# LCD-Touch.net
KiCad netlist of a schematic drawn in Altium Designer
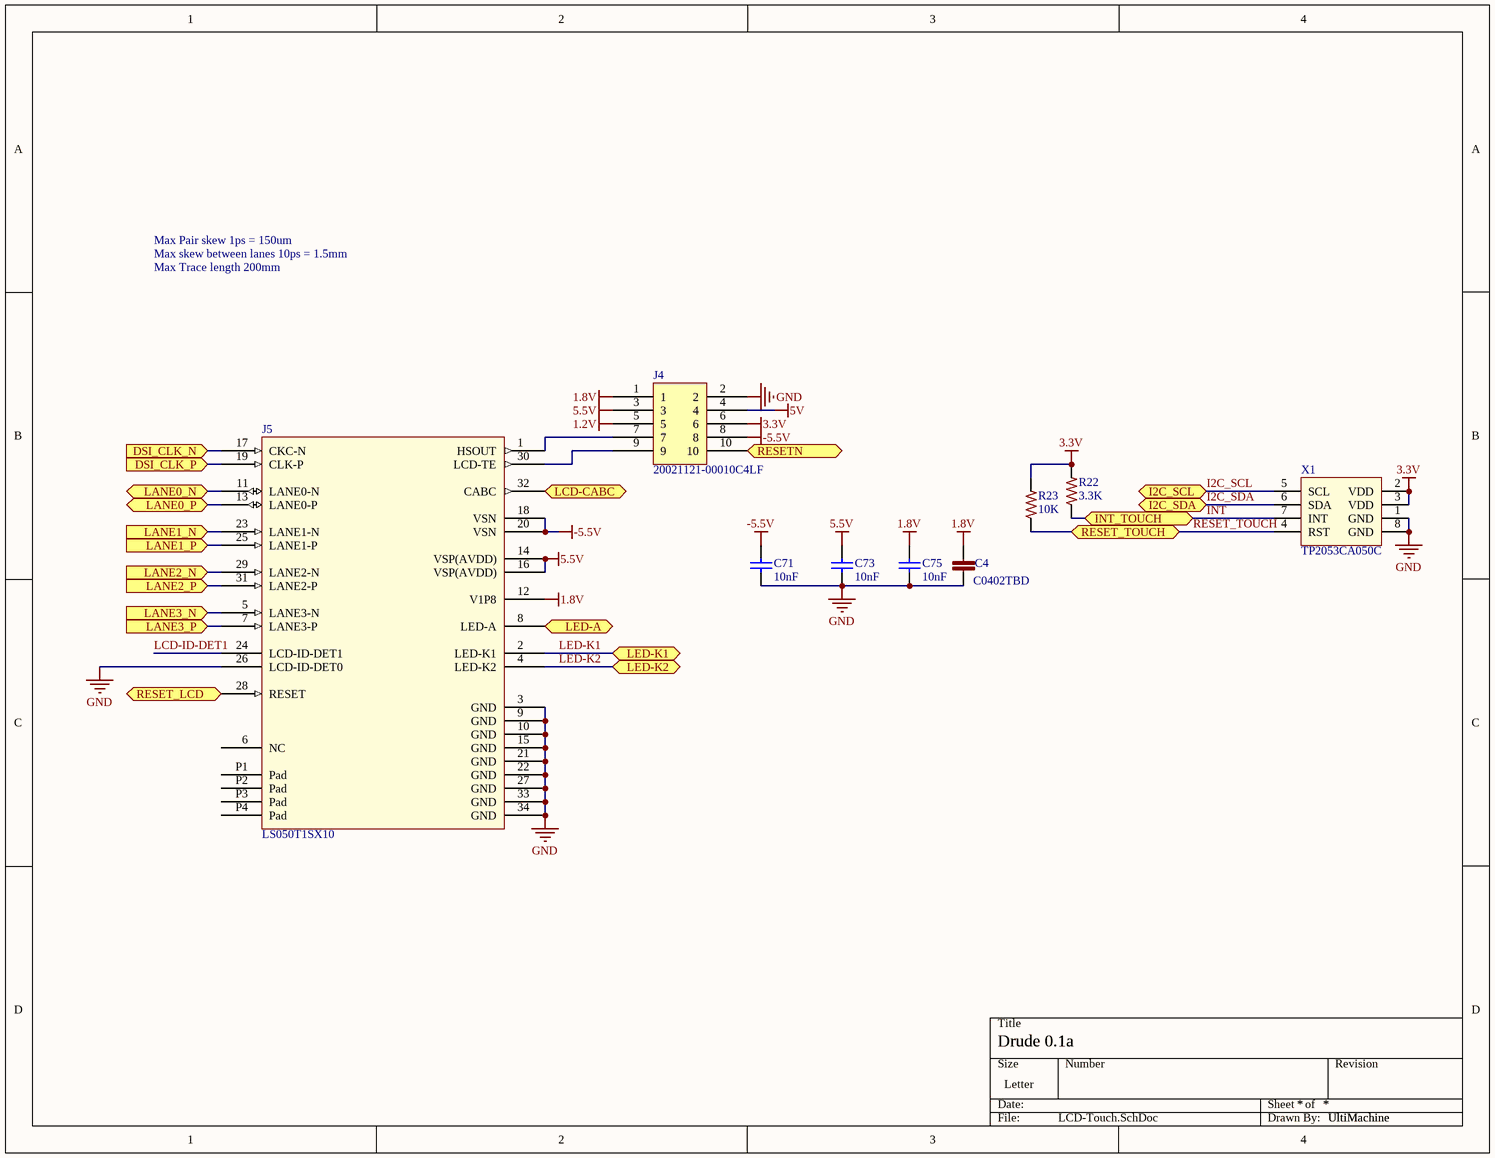
[diagram p0: LCD-Touch.SchDoc]

(export (version "E")
  (design (tool "Eeschema 10.0.6"))
  (components
    (comp (ref "C4")
      (value "C0402TBD")
      (footprint "C0402")
      (description "Capacitor Non Polarized")
      (fields (field (name "PUBLISHER") "UltiMachine"))
      (libsource (lib "3Delight") (part "C0402TBD"))
    )
    (comp (ref "C71")
      (value "10nF")
      (footprint "C0402")
      (description "CAP CER 10nF 50V X7R 0402")
      (fields
        (field (name "MFR PART #") "GRM155R71H103JA88D")
        (field (name "MFR") "Murata")
        (field (name "PUBLISHER") "Ultimachine")
      )
      (libsource (lib "hmi") (part "GRM155R71H103JA88D"))
    )
    (comp (ref "C73")
      (value "10nF")
      (footprint "C0402")
      (description "CAP CER 10nF 50V X7R 0402")
      (fields
        (field (name "MFR PART #") "GRM155R71H103JA88D")
        (field (name "MFR") "Murata")
        (field (name "PUBLISHER") "Ultimachine")
      )
      (libsource (lib "hmi") (part "GRM155R71H103JA88D"))
    )
    (comp (ref "C75")
      (value "10nF")
      (footprint "C0402")
      (description "CAP CER 10nF 50V X7R 0402")
      (fields
        (field (name "MFR PART #") "GRM155R71H103JA88D")
        (field (name "MFR") "Murata")
        (field (name "PUBLISHER") "Ultimachine")
      )
      (libsource (lib "hmi") (part "GRM155R71H103JA88D"))
    )
    (comp (ref "J4")
      (value "20021121-00010C4LF")
      (footprint "FTSH-105-XX-X-DV")
      (libsource (lib "Adams Altium Library") (part "ARM Cortex JTAG-DEBUG Header"))
    )
    (comp (ref "J5")
      (value "LS050T1SX10")
      (footprint "504208-3410")
      (description "5\"HD LCD Module connector")
      (libsource (lib "hmi") (part "LS050T1SX10"))
    )
    (comp (ref "R22")
      (value "3.3K")
      (footprint "R0603")
      (description "RES 0603 3.3K 100mW 1%")
      (fields
        (field (name "MANUFACTURERPARTNUMBER") "ERJ-3EKF1002V")
        (field (name "PUBLISHER") "UltiMachine")
      )
      (libsource (lib "hmi") (part "ERJ-3GEYJ332V"))
    )
    (comp (ref "R23")
      (value "10K")
      (footprint "R0402")
      (description "RES SMD 10K OHM 1% 1/16W 0402")
      (fields
        (field (name "MANUFACTURERPARTNUMBER") "RC0402FR-0710KP")
        (field (name "PUBLISHER") "UltiMachine")
      )
      (libsource (lib "3Delight") (part "RC0402FR-0710KP"))
    )
    (comp (ref "X1")
      (value "TP2053CA050C")
      (footprint "FFC8x05-top")
      (description "UltiMachine 5\" HD Touch Interface")
      (libsource (lib "hmi") (part "TP2053CA050C"))
    )
  )
  (nets
    (net (code "1") (name "-5.5V") (class "Default")
      (node (ref "C71") (pin "2") (pinfunction "2_2") (pintype "passive"))
      (node (ref "J4") (pin "8") (pinfunction "8_8") (pintype "passive"))
      (node (ref "J5") (pin "18") (pinfunction "VSN_18") (pintype "power_in"))
      (node (ref "J5") (pin "20") (pinfunction "VSN_20") (pintype "power_in"))
    )
    (net (code "2") (name "/DSI_CLK_N") (class "Default")
      (node (ref "J5") (pin "17") (pinfunction "CKC-N_17") (pintype "input"))
    )
    (net (code "3") (name "/DSI_CLK_P") (class "Default")
      (node (ref "J5") (pin "19") (pinfunction "CLK-P_19") (pintype "input"))
    )
    (net (code "4") (name "/I2C_SCL") (class "Default")
      (node (ref "X1") (pin "5") (pinfunction "SCL_5") (pintype "power_in"))
    )
    (net (code "5") (name "/I2C_SDA") (class "Default")
      (node (ref "X1") (pin "6") (pinfunction "SDA_6") (pintype "power_in"))
    )
    (net (code "6") (name "/INT") (class "Default")
      (node (ref "R22") (pin "1") (pinfunction "1_1") (pintype "passive"))
      (node (ref "X1") (pin "7") (pinfunction "INT_7") (pintype "power_in"))
    )
    (net (code "7") (name "/LANE0_N") (class "Default")
      (node (ref "J5") (pin "11") (pinfunction "LANE0-N_11") (pintype "bidirectional"))
    )
    (net (code "8") (name "/LANE0_P") (class "Default")
      (node (ref "J5") (pin "13") (pinfunction "LANE0-P_13") (pintype "bidirectional"))
    )
    (net (code "9") (name "/LANE1_N") (class "Default")
      (node (ref "J5") (pin "23") (pinfunction "LANE1-N_23") (pintype "input"))
    )
    (net (code "10") (name "/LANE1_P") (class "Default")
      (node (ref "J5") (pin "25") (pinfunction "LANE1-P_25") (pintype "input"))
    )
    (net (code "11") (name "/LANE2_N") (class "Default")
      (node (ref "J5") (pin "29") (pinfunction "LANE2-N_29") (pintype "input"))
    )
    (net (code "12") (name "/LANE2_P") (class "Default")
      (node (ref "J5") (pin "31") (pinfunction "LANE2-P_31") (pintype "input"))
    )
    (net (code "13") (name "/LANE3_N") (class "Default")
      (node (ref "J5") (pin "5") (pinfunction "LANE3-N_5") (pintype "input"))
    )
    (net (code "14") (name "/LANE3_P") (class "Default")
      (node (ref "J5") (pin "7") (pinfunction "LANE3-P_7") (pintype "input"))
    )
    (net (code "15") (name "/LCD-CABC") (class "Default")
      (node (ref "J5") (pin "32") (pinfunction "CABC_32") (pintype "output"))
    )
    (net (code "16") (name "/LCD-ID-DET1") (class "Default")
      (node (ref "J5") (pin "24") (pinfunction "LCD-ID-DET1_24") (pintype "passive"))
    )
    (net (code "17") (name "/LED-A") (class "Default")
      (node (ref "J5") (pin "8") (pinfunction "LED-A_8") (pintype "power_in"))
    )
    (net (code "18") (name "/LED-K1") (class "Default")
      (node (ref "J5") (pin "2") (pinfunction "LED-K1_2") (pintype "power_in"))
    )
    (net (code "19") (name "/LED-K2") (class "Default")
      (node (ref "J5") (pin "4") (pinfunction "LED-K2_4") (pintype "power_in"))
    )
    (net (code "20") (name "/RESETN") (class "Default")
      (node (ref "J4") (pin "10") (pinfunction "10_10") (pintype "passive"))
    )
    (net (code "21") (name "/RESET_LCD") (class "Default")
      (node (ref "J5") (pin "28") (pinfunction "RESET_28") (pintype "input"))
    )
    (net (code "22") (name "/RESET_TOUCH") (class "Default")
      (node (ref "R23") (pin "1") (pinfunction "1_1") (pintype "passive"))
      (node (ref "X1") (pin "4") (pinfunction "RST_4") (pintype "power_in"))
    )
    (net (code "23") (name "1.2V") (class "Default")
      (node (ref "J4") (pin "5") (pinfunction "5_5") (pintype "passive"))
    )
    (net (code "24") (name "1.8V") (class "Default")
      (node (ref "C4") (pin "1") (pinfunction "1_1") (pintype "passive"))
      (node (ref "C75") (pin "2") (pinfunction "2_2") (pintype "passive"))
      (node (ref "J4") (pin "1") (pinfunction "1_1") (pintype "passive"))
      (node (ref "J5") (pin "12") (pinfunction "V1P8_12") (pintype "power_in"))
    )
    (net (code "25") (name "3.3V") (class "Default")
      (node (ref "J4") (pin "6") (pinfunction "6_6") (pintype "passive"))
      (node (ref "R22") (pin "2") (pinfunction "2_2") (pintype "passive"))
      (node (ref "R23") (pin "2") (pinfunction "2_2") (pintype "passive"))
      (node (ref "X1") (pin "2") (pinfunction "VDD_2") (pintype "power_in"))
      (node (ref "X1") (pin "3") (pinfunction "VDD_3") (pintype "power_in"))
    )
    (net (code "26") (name "5.5V") (class "Default")
      (node (ref "C73") (pin "2") (pinfunction "2_2") (pintype "passive"))
      (node (ref "J4") (pin "3") (pinfunction "3_3") (pintype "passive"))
      (node (ref "J5") (pin "14") (pinfunction "VSP(AVDD)_14") (pintype "power_in"))
      (node (ref "J5") (pin "16") (pinfunction "VSP(AVDD)_16") (pintype "power_in"))
    )
    (net (code "27") (name "5V") (class "Default")
      (node (ref "J4") (pin "4") (pinfunction "4_4") (pintype "passive"))
    )
    (net (code "28") (name "GND") (class "Default")
      (node (ref "C4") (pin "2") (pinfunction "2_2") (pintype "passive"))
      (node (ref "C71") (pin "1") (pinfunction "1_1") (pintype "passive"))
      (node (ref "C73") (pin "1") (pinfunction "1_1") (pintype "passive"))
      (node (ref "C75") (pin "1") (pinfunction "1_1") (pintype "passive"))
      (node (ref "J4") (pin "2") (pinfunction "2_2") (pintype "passive"))
      (node (ref "J5") (pin "10") (pinfunction "GND_10") (pintype "power_in"))
      (node (ref "J5") (pin "15") (pinfunction "GND_15") (pintype "power_in"))
      (node (ref "J5") (pin "21") (pinfunction "GND_21") (pintype "power_in"))
      (node (ref "J5") (pin "22") (pinfunction "GND_22") (pintype "power_in"))
      (node (ref "J5") (pin "26") (pinfunction "LCD-ID-DET0_26") (pintype "passive"))
      (node (ref "J5") (pin "27") (pinfunction "GND_27") (pintype "power_in"))
      (node (ref "J5") (pin "3") (pinfunction "GND_3") (pintype "power_in"))
      (node (ref "J5") (pin "33") (pinfunction "GND_33") (pintype "power_in"))
      (node (ref "J5") (pin "34") (pinfunction "GND_34") (pintype "power_in"))
      (node (ref "J5") (pin "9") (pinfunction "GND_9") (pintype "power_in"))
      (node (ref "X1") (pin "1") (pinfunction "GND_1") (pintype "power_in"))
      (node (ref "X1") (pin "8") (pinfunction "GND_8") (pintype "power_in"))
    )
    (net (code "29") (name "Net-(J5-HSOUT)") (class "Default")
      (node (ref "J4") (pin "7") (pinfunction "7_7") (pintype "passive"))
      (node (ref "J5") (pin "1") (pinfunction "HSOUT_1") (pintype "output"))
    )
    (net (code "30") (name "Net-(J5-LCD-TE)") (class "Default")
      (node (ref "J4") (pin "9") (pinfunction "9_9") (pintype "passive"))
      (node (ref "J5") (pin "30") (pinfunction "LCD-TE_30") (pintype "output"))
    )
    (net (code "31") (name "unconnected-(J5-NC-Pad6)") (class "Default")
      (node (ref "J5") (pin "6") (pinfunction "NC_6") (pintype "passive"))
    )
    (net (code "32") (name "unconnected-(J5-Pad-PadP1)") (class "Default")
      (node (ref "J5") (pin "P1") (pinfunction "Pad_P1") (pintype "passive"))
    )
    (net (code "33") (name "unconnected-(J5-Pad-PadP2)") (class "Default")
      (node (ref "J5") (pin "P2") (pinfunction "Pad_P2") (pintype "passive"))
    )
    (net (code "34") (name "unconnected-(J5-Pad-PadP3)") (class "Default")
      (node (ref "J5") (pin "P3") (pinfunction "Pad_P3") (pintype "passive"))
    )
    (net (code "35") (name "unconnected-(J5-Pad-PadP4)") (class "Default")
      (node (ref "J5") (pin "P4") (pinfunction "Pad_P4") (pintype "passive"))
    )
  )
)
